# 200415_eAR_ECU_PX_Sensor_PTH_R00.net
KiCad netlist of a schematic drawn in EAGLE
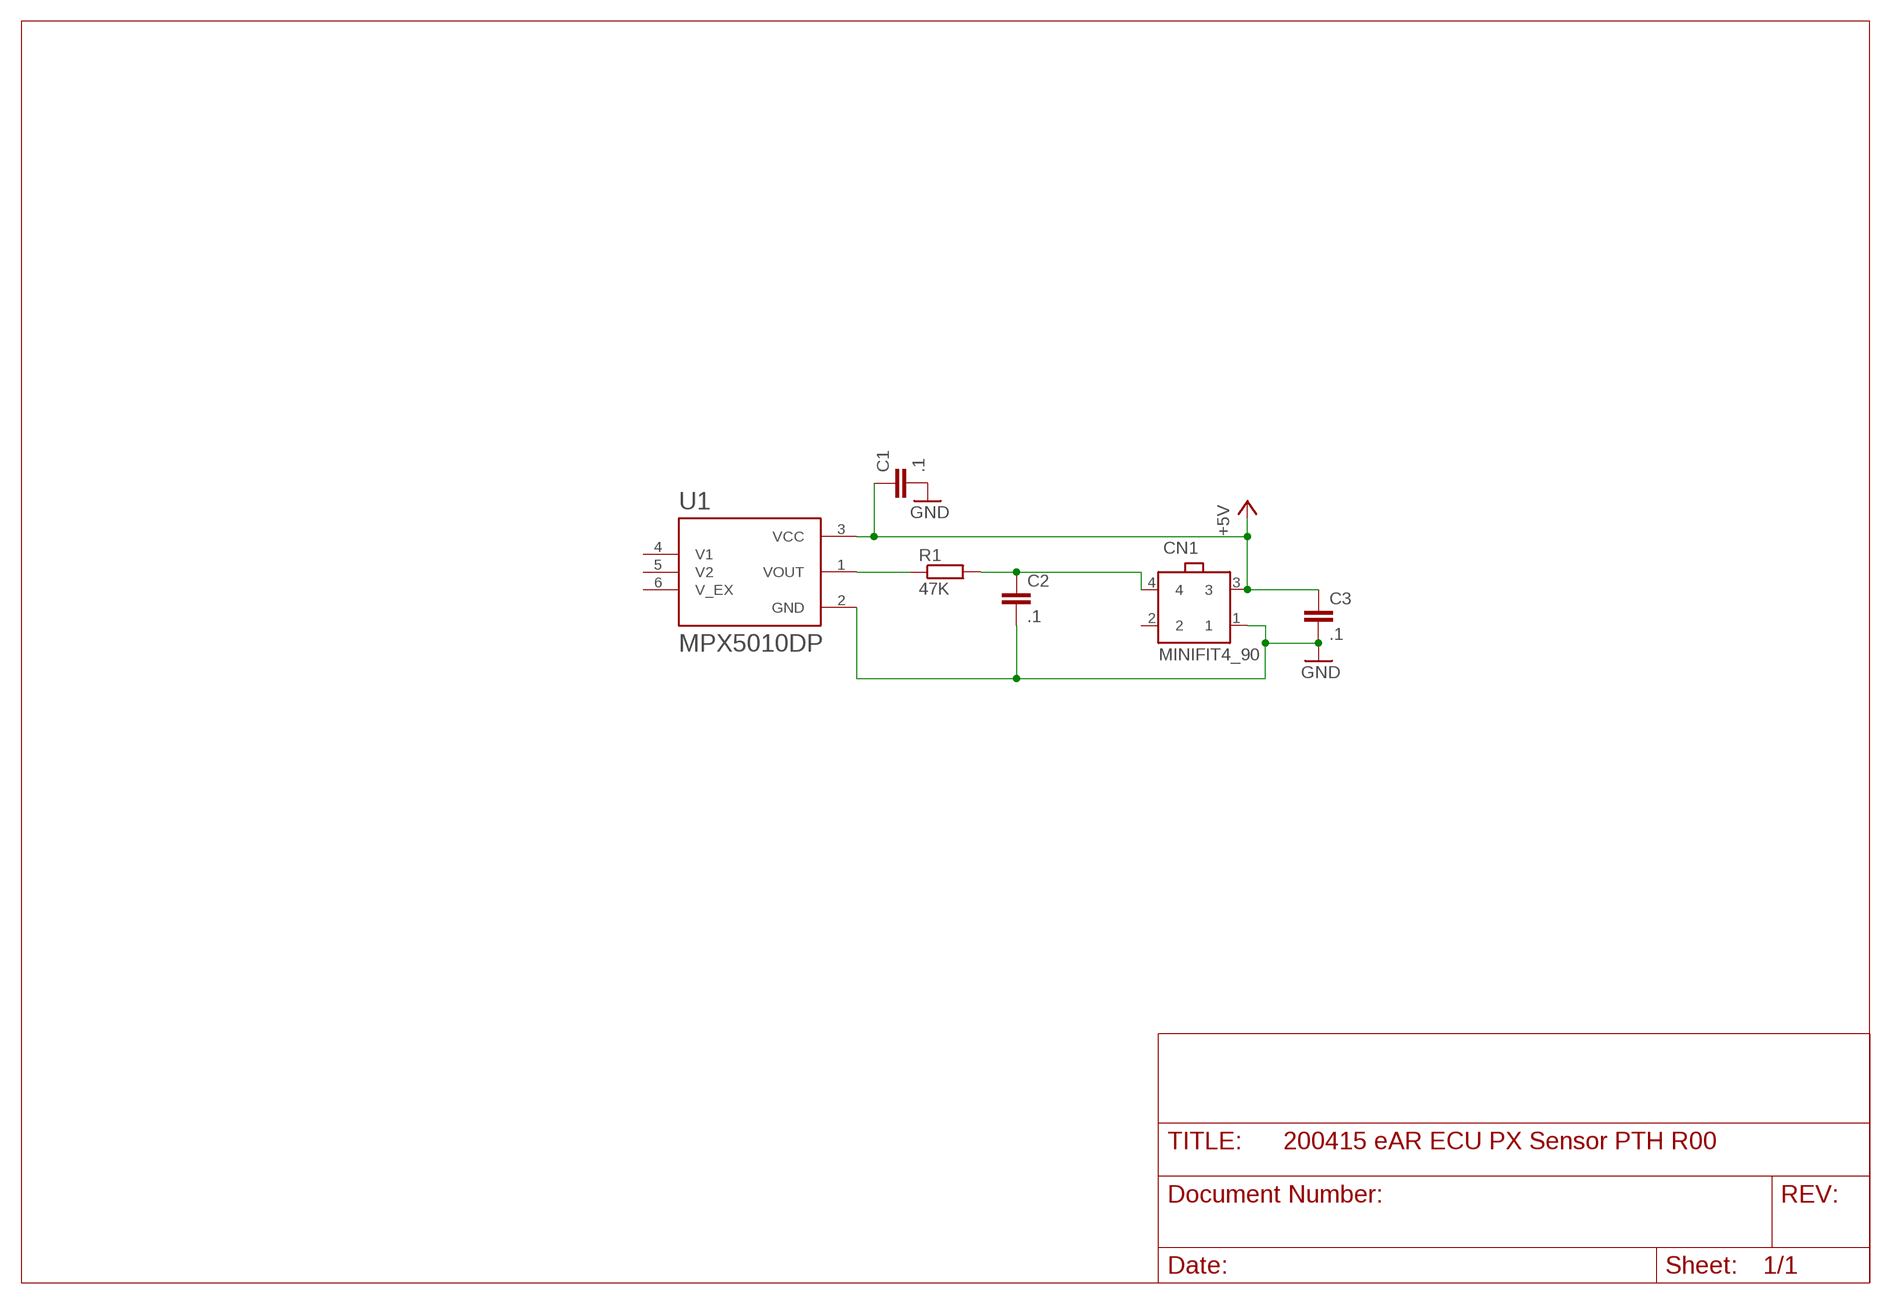
[diagram p0: schematic, sheet 1]

(export (version "E")
  (design (tool "Eeschema 10.0.6"))
  (components
    (comp (ref "C1")
      (value ".1")
      (footprint "eagle-import:C050-025X075")
      (libsource (lib "eagle-import") (part "C-EU050-025X075"))
    )
    (comp (ref "C2")
      (value ".1")
      (footprint "eagle-import:C050-025X075")
      (libsource (lib "eagle-import") (part "C-EU050-025X075"))
    )
    (comp (ref "C3")
      (value ".1")
      (footprint "eagle-import:C050-025X075")
      (libsource (lib "eagle-import") (part "C-EU050-025X075"))
    )
    (comp (ref "CN1")
      (value "MINIFIT4_90")
      (footprint "eagle-import:MINIFIT4_90")
      (libsource (lib "eagle-import") (part "MINIFIT4_90"))
    )
    (comp (ref "R1")
      (value "47K")
      (footprint "eagle-import:0207_10")
      (libsource (lib "eagle-import") (part "R-EU_0207/10"))
    )
    (comp (ref "U1")
      (value "MPX5010DP")
      (footprint "eagle-import:XDCR_MPX5010DP")
      (fields (field (name "MF") "NXP USA"))
      (libsource (lib "eagle-import") (part "MPX5010DP"))
    )
  )
  (nets
    (net (code "1") (name "+5V") (class "Default")
      (node (ref "C1") (pin "1") (pinfunction "1_1") (pintype "passive"))
      (node (ref "C3") (pin "1") (pinfunction "1_1") (pintype "passive"))
      (node (ref "CN1") (pin "3") (pinfunction "3_3") (pintype "bidirectional"))
      (node (ref "U1") (pin "3") (pinfunction "VCC_3") (pintype "power_in"))
    )
    (net (code "2") (name "GND") (class "Default")
      (node (ref "C1") (pin "2") (pinfunction "2_2") (pintype "passive"))
      (node (ref "C2") (pin "2") (pinfunction "2_2") (pintype "passive"))
      (node (ref "C3") (pin "2") (pinfunction "2_2") (pintype "passive"))
      (node (ref "CN1") (pin "1") (pinfunction "1_1") (pintype "bidirectional"))
      (node (ref "U1") (pin "2") (pinfunction "GND_2") (pintype "power_in"))
    )
    (net (code "3") (name "Net-(C2-Pad1)") (class "Default")
      (node (ref "C2") (pin "1") (pinfunction "1_1") (pintype "passive"))
      (node (ref "CN1") (pin "4") (pinfunction "4_4") (pintype "bidirectional"))
      (node (ref "R1") (pin "2") (pinfunction "2_2") (pintype "passive"))
    )
    (net (code "4") (name "Net-(U1-VOUT)") (class "Default")
      (node (ref "R1") (pin "1") (pinfunction "1_1") (pintype "passive"))
      (node (ref "U1") (pin "1") (pinfunction "VOUT_1") (pintype "output"))
    )
    (net (code "5") (name "unconnected-(CN1-Pad2)") (class "Default")
      (node (ref "CN1") (pin "2") (pinfunction "2_2") (pintype "bidirectional"))
    )
    (net (code "6") (name "unconnected-(U1-V1-Pad4)") (class "Default")
      (node (ref "U1") (pin "4") (pinfunction "V1_4") (pintype "no_connect"))
    )
    (net (code "7") (name "unconnected-(U1-V2-Pad5)") (class "Default")
      (node (ref "U1") (pin "5") (pinfunction "V2_5") (pintype "no_connect"))
    )
    (net (code "8") (name "unconnected-(U1-V_EX-Pad6)") (class "Default")
      (node (ref "U1") (pin "6") (pinfunction "V_EX_6") (pintype "no_connect"))
    )
  )
)
